# RS485_Communication_Layer.net
KiCad netlist of a schematic drawn in Altium Designer
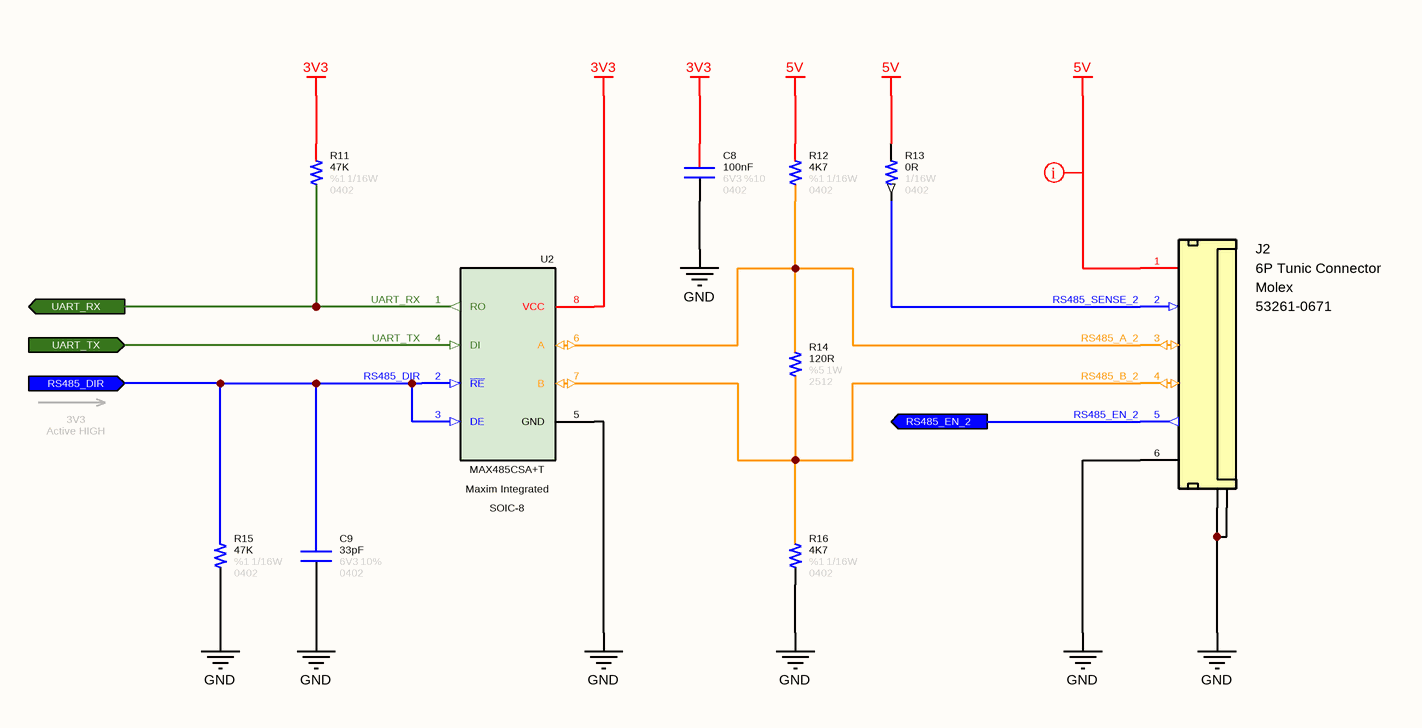
[diagram p0: RS485 Communication Layer.SchDoc]

(export (version "E")
  (design (tool "Eeschema 10.0.6"))
  (components
    (comp (ref "C8")
      (value "100nF")
      (footprint "CAPACITOR_0402")
      (description "Capacitor - 100nF [0402-6V3] (Ceramic)")
      (fields
        (field (name "MANUFACTURER PART NUMBER") "04026D104KAT4A")
        (field (name "TOLERANCE") "%10")
        (field (name "VOLTAGE") "6V3")
        (field (name "CASE") "0402")
        (field (name "Comment") "Capacitor - 100nF [0402] (Ceramic)")
      )
      (libsource (lib "Akkoyun") (part "Capacitor - 100nF [0402-6V3]"))
    )
    (comp (ref "C9")
      (value "33pF")
      (footprint "CAPACITOR_0402")
      (description "Capacitor - 33pF [0402] (Ceramic)")
      (fields
        (field (name "MANUFACTURER PART NUMBER") "C0402C330J9RACAUTO")
        (field (name "TOLERANCE") "10%")
        (field (name "CASE") "0402")
        (field (name "VOLTAGE") "6V3")
      )
      (libsource (lib "Akkoyun") (part "Capacitor - 33pF [0402-6V3]"))
    )
    (comp (ref "J2")
      (value "6P Tunic Connector")
      (footprint "Connector_Tunic 6P")
      (description "Mini Tunic Connector with 6P")
      (fields
        (field (name "MANUFACTURER PART NUMBER") "53261-0671")
        (field (name "MANUFACTURER NAME") "Molex")
      )
      (libsource (lib "Akkoyun") (part "Connector - Mini Tunic 6P (1.25)"))
    )
    (comp (ref "R11")
      (value "47K")
      (footprint "RESISTOR_0402")
      (description "Thick Film Resistors - SMD 1/16 W 47 KOhm 1%")
      (fields
        (field (name "MANUFACTURER PART NUMBER") "CRCW040247K0FKED")
        (field (name "TOLERANCE") "%1")
        (field (name "CASE") "0402")
        (field (name "POWER") "1/16W")
        (field (name "Comment") "47K - 0402 - %1 - 1/16W")
      )
      (libsource (lib "Akkoyun") (part "Resistor - 47K [0402]"))
    )
    (comp (ref "R12")
      (value "4K7")
      (footprint "RESISTOR_0402")
      (description "Thick Film Resistors - SMD 1/16 W 4.7 KOhm 1%")
      (fields
        (field (name "MANUFACTURER PART NUMBER") "CRCW04024K70FKED")
        (field (name "TOLERANCE") "%1")
        (field (name "CASE") "0402")
        (field (name "POWER") "1/16W")
        (field (name "Comment") "4K7 - 0402 - %1 - 1/16W")
      )
      (libsource (lib "Akkoyun") (part "Resistor - 4K7 [0402]"))
    )
    (comp (ref "R13")
      (value "0R")
      (footprint "RESISTOR_0402")
      (description "Thick Film Resistors - SMD 1/16 W 0 Ohm")
      (fields
        (field (name "MANUFACTURER PART NUMBER") "CRCW04020000Z0ED")
        (field (name "CASE") "0402")
        (field (name "POWER") "1/16W")
        (field (name "Comment") "0R - 0402 - %1 - 1/16W")
      )
      (libsource (lib "Akkoyun") (part "Resistor - 0R [0402]"))
    )
    (comp (ref "R14")
      (value "120R")
      (footprint "RESISTOR_2512")
      (description "Thick Film Resistors - SMD 1 W 120 Ohm 5%")
      (fields
        (field (name "MANUFACTURER PART NUMBER") "RC2512JK-07120RL")
        (field (name "TOLERANCE") "%5")
        (field (name "CASE") "2512")
        (field (name "POWER") "1W")
        (field (name "Comment") "120R - 2512 - %5 - 1W")
      )
      (libsource (lib "Akkoyun") (part "Resistor - 120R [2512]"))
    )
    (comp (ref "R15")
      (value "47K")
      (footprint "RESISTOR_0402")
      (description "Thick Film Resistors - SMD 1/16 W 47 KOhm 1%")
      (fields
        (field (name "MANUFACTURER PART NUMBER") "CRCW040247K0FKED")
        (field (name "TOLERANCE") "%1")
        (field (name "CASE") "0402")
        (field (name "POWER") "1/16W")
        (field (name "Comment") "47K - 0402 - %1 - 1/16W")
      )
      (libsource (lib "Akkoyun") (part "Resistor - 47K [0402]"))
    )
    (comp (ref "R16")
      (value "4K7")
      (footprint "RESISTOR_0402")
      (description "Thick Film Resistors - SMD 1/16 W 4.7 KOhm 1%")
      (fields
        (field (name "MANUFACTURER PART NUMBER") "CRCW04024K70FKED")
        (field (name "TOLERANCE") "%1")
        (field (name "CASE") "0402")
        (field (name "POWER") "1/16W")
        (field (name "Comment") "4K7 - 0402 - %1 - 1/16W")
      )
      (libsource (lib "Akkoyun") (part "Resistor - 4K7 [0402]"))
    )
    (comp (ref "U2")
      (value "RS485 Modulator")
      (footprint "SOP-8L (AZRS3080E)")
      (description "RS-422/RS-485 Interface IC Low-Power, Slew-Rate-Limited RS-485/RS-422 Transceivers")
      (fields
        (field (name "CASE") "SOIC-8")
        (field (name "MANUFACTURER PART NUMBER") "MAX485CSA+T")
        (field (name "MANUFACTURER NAME") "Maxim Integrated")
      )
      (libsource (lib "Akkoyun") (part "IC - MAX485CSA+T"))
    )
  )
  (nets
    (net (code "1") (name "/RS485_A_2") (class "Default")
      (node (ref "J2") (pin "3") (pinfunction "RS485-A_3") (pintype "bidirectional"))
      (node (ref "R12") (pin "1") (pinfunction "1_1") (pintype "passive"))
      (node (ref "R14") (pin "2") (pinfunction "2_2") (pintype "passive"))
      (node (ref "U2") (pin "6") (pinfunction "A_6") (pintype "bidirectional"))
    )
    (net (code "2") (name "/RS485_B_2") (class "Default")
      (node (ref "J2") (pin "4") (pinfunction "RS485-B_4") (pintype "bidirectional"))
      (node (ref "R14") (pin "1") (pinfunction "1_1") (pintype "passive"))
      (node (ref "R16") (pin "2") (pinfunction "2_2") (pintype "passive"))
      (node (ref "U2") (pin "7") (pinfunction "B_7") (pintype "bidirectional"))
    )
    (net (code "3") (name "/RS485_DIR") (class "Default")
      (node (ref "C9") (pin "2") (pinfunction "2_2") (pintype "passive"))
      (node (ref "R15") (pin "2") (pinfunction "2_2") (pintype "passive"))
      (node (ref "U2") (pin "2") (pinfunction "~{RE}_2") (pintype "input"))
      (node (ref "U2") (pin "3") (pinfunction "DE_3") (pintype "input"))
    )
    (net (code "4") (name "/RS485_EN_2") (class "Default")
      (node (ref "J2") (pin "5") (pinfunction "INT_5") (pintype "output"))
    )
    (net (code "5") (name "/RS485_SENSE_2") (class "Default")
      (node (ref "J2") (pin "2") (pinfunction "Sense_2") (pintype "input"))
      (node (ref "R13") (pin "1") (pinfunction "1_1") (pintype "output"))
    )
    (net (code "6") (name "/UART_RX") (class "Default")
      (node (ref "R11") (pin "1") (pinfunction "1_1") (pintype "passive"))
      (node (ref "U2") (pin "1") (pinfunction "RO_1") (pintype "output"))
    )
    (net (code "7") (name "/UART_TX") (class "Default")
      (node (ref "U2") (pin "4") (pinfunction "DI_4") (pintype "input"))
    )
    (net (code "8") (name "3V3") (class "Default")
      (node (ref "C8") (pin "2") (pinfunction "2_2") (pintype "passive"))
      (node (ref "R11") (pin "2") (pinfunction "2_2") (pintype "passive"))
      (node (ref "U2") (pin "8") (pinfunction "VCC_8") (pintype "power_in"))
    )
    (net (code "9") (name "5V") (class "Default")
      (node (ref "J2") (pin "1") (pinfunction "5V_1") (pintype "power_in"))
      (node (ref "R12") (pin "2") (pinfunction "2_2") (pintype "passive"))
      (node (ref "R13") (pin "2") (pinfunction "2_2") (pintype "passive"))
    )
    (net (code "10") (name "GND") (class "Default")
      (node (ref "C8") (pin "1") (pinfunction "1_1") (pintype "passive"))
      (node (ref "C9") (pin "1") (pinfunction "1_1") (pintype "passive"))
      (node (ref "J2") (pin "6") (pinfunction "GND_6") (pintype "power_in"))
      (node (ref "J2") (pin "7") (pinfunction "GND_7") (pintype "passive"))
      (node (ref "J2") (pin "8") (pinfunction "GND_8") (pintype "passive"))
      (node (ref "R15") (pin "1") (pinfunction "1_1") (pintype "passive"))
      (node (ref "R16") (pin "1") (pinfunction "1_1") (pintype "passive"))
      (node (ref "U2") (pin "5") (pinfunction "GND_5") (pintype "passive"))
    )
  )
)
